# FLR_-_Schematic.net
KiCad netlist of a schematic drawn in EAGLE
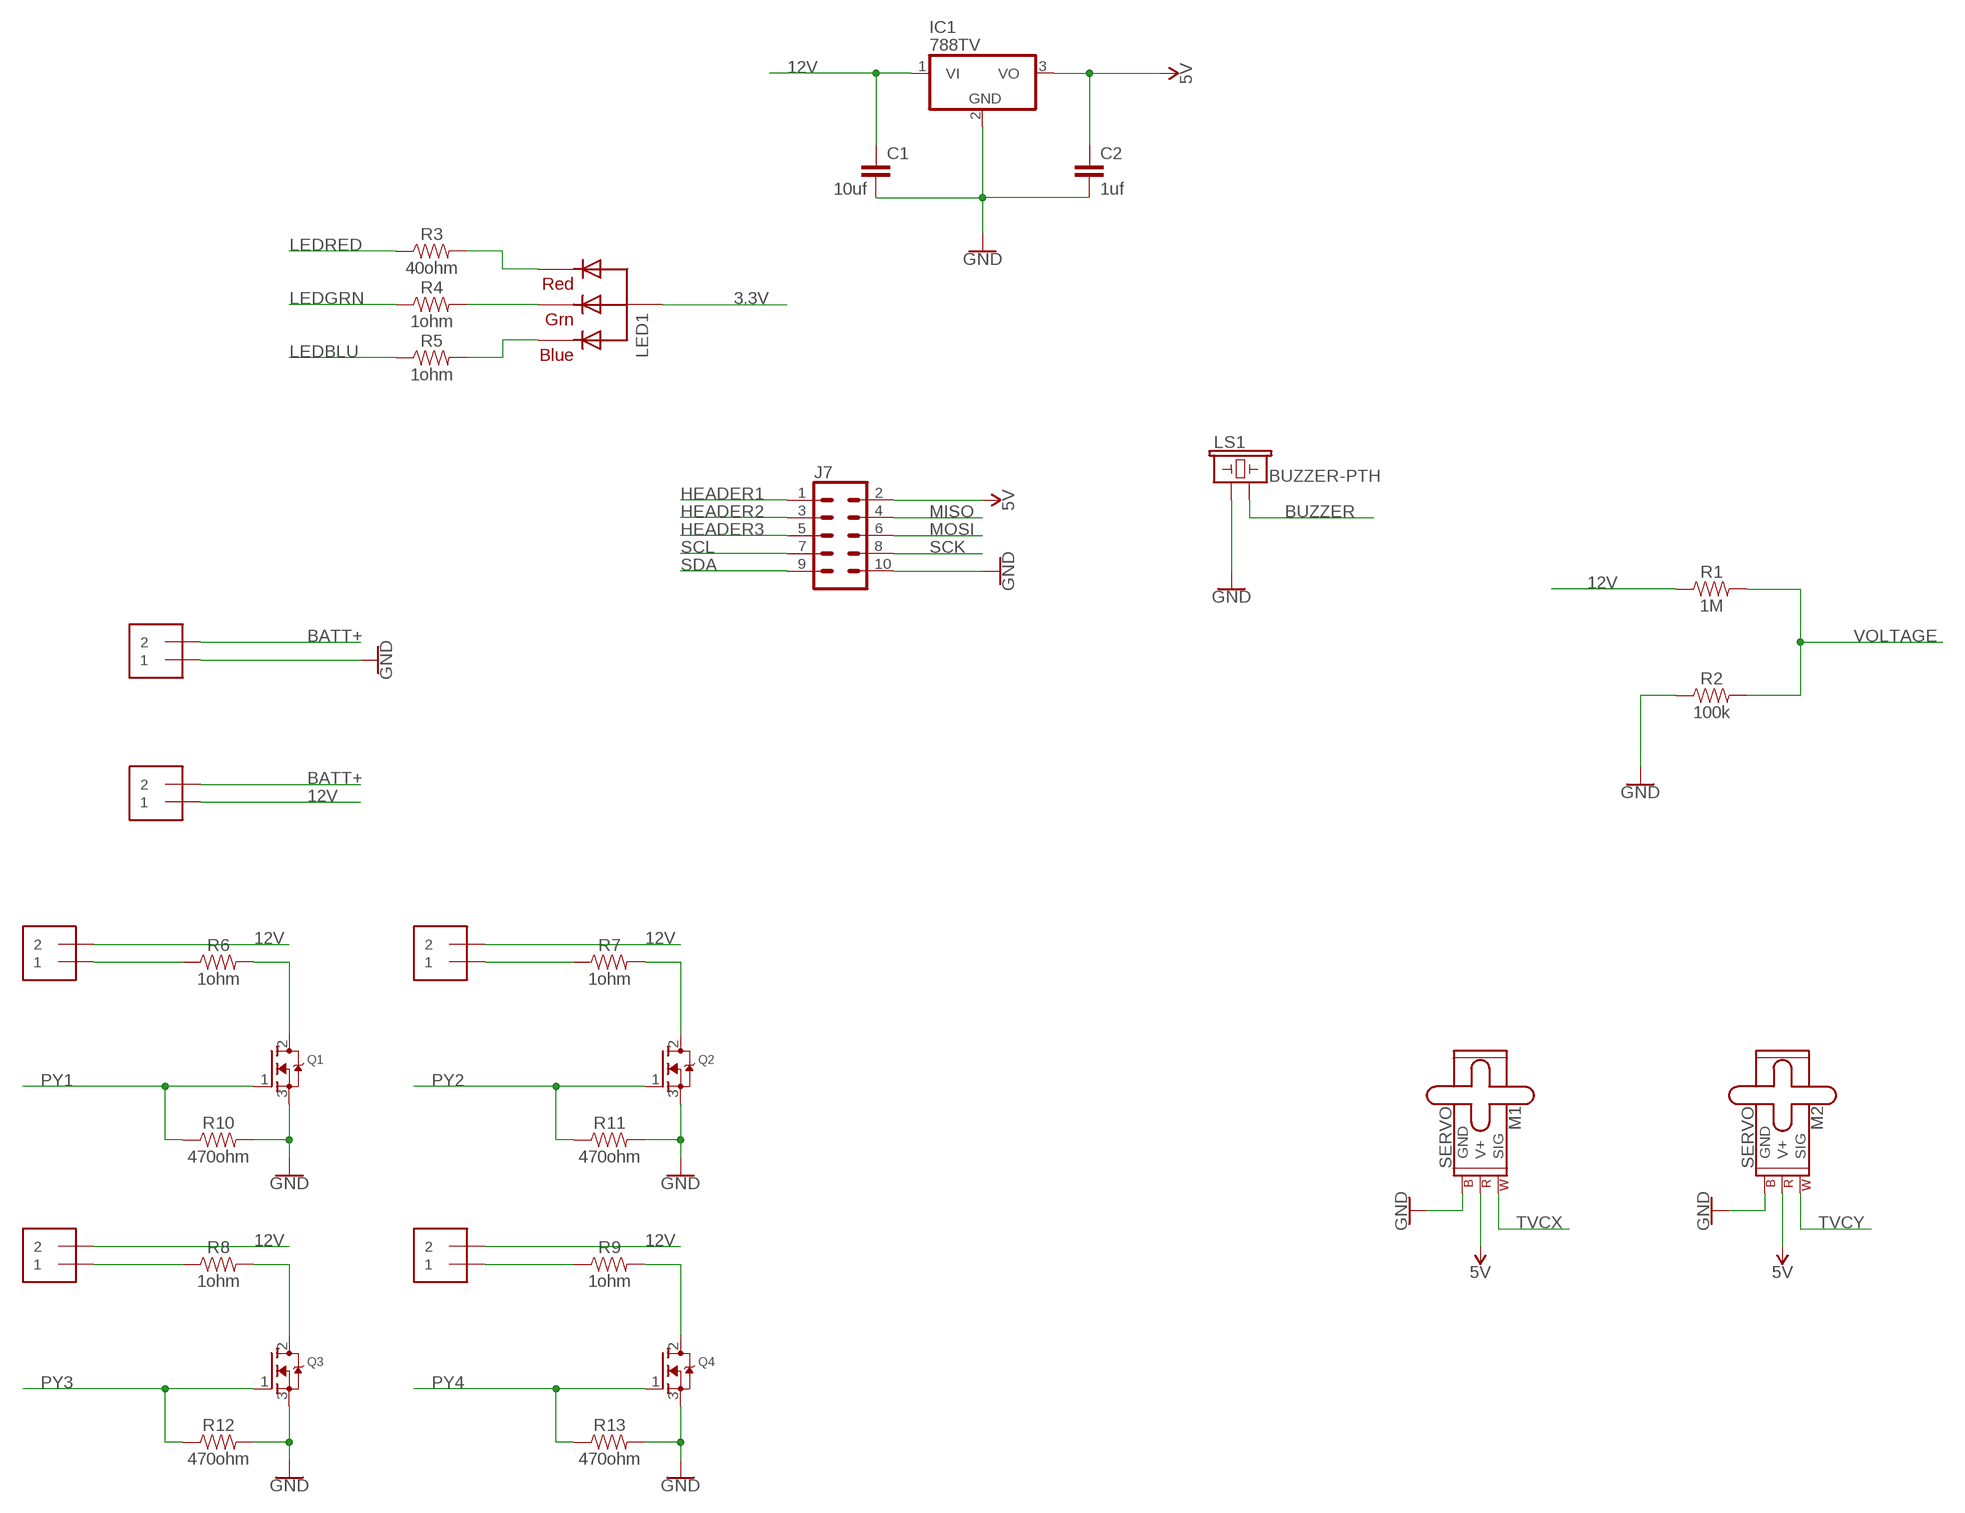
[diagram p0: schematic, sheet 1, part 1 of 2]
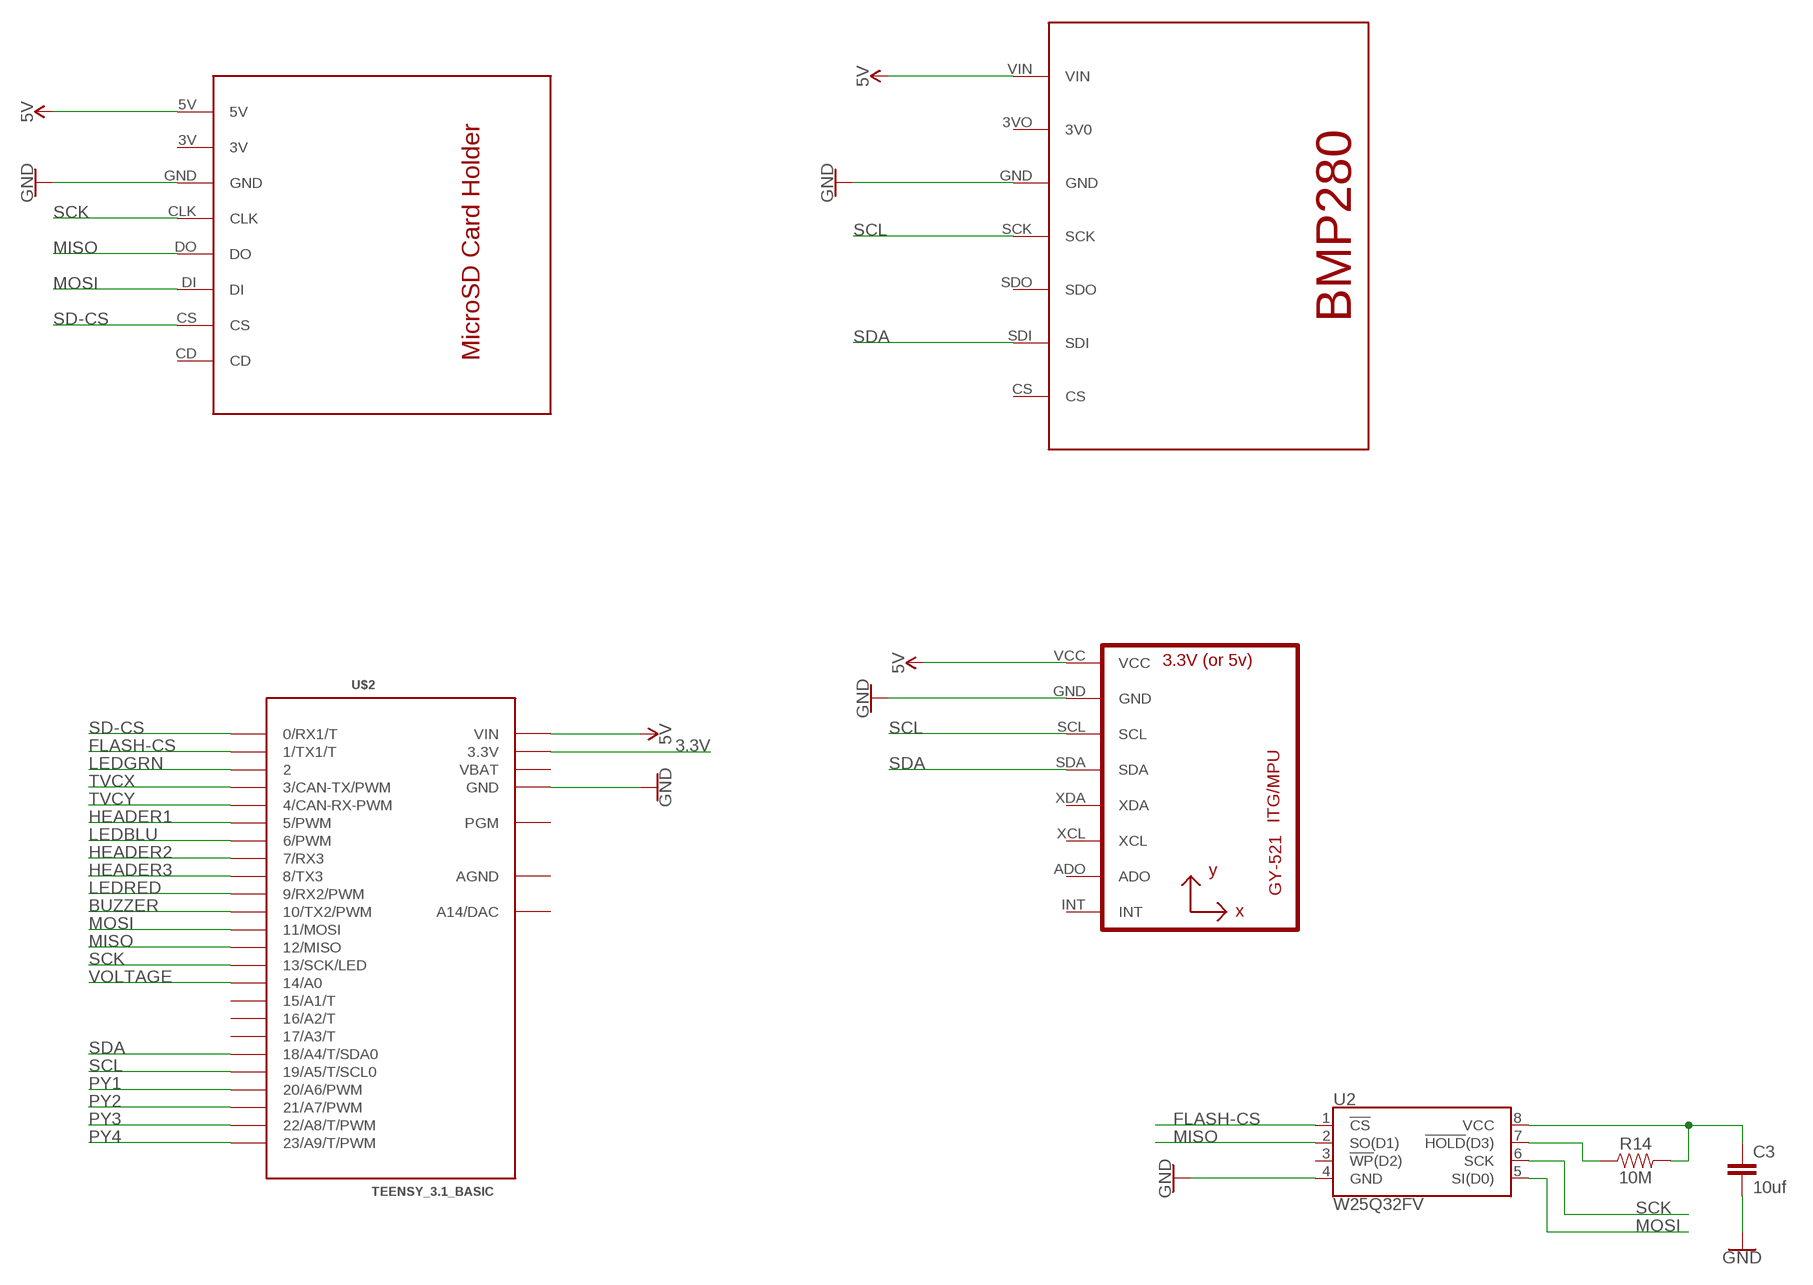
[diagram p1: schematic, sheet 1, part 2 of 2]

(export (version "E")
  (design (tool "Eeschema 10.0.6"))
  (components
    (comp (ref "C1")
      (value "10uf")
      (footprint "eagle-import:CAP-PTH-2.54")
      (libsource (lib "eagle-import") (part "22PF-PTH-2.54MM-200V-5%"))
    )
    (comp (ref "C2")
      (value "1uf")
      (footprint "eagle-import:CAP-PTH-2.54")
      (libsource (lib "eagle-import") (part "22PF-PTH-2.54MM-200V-5%"))
    )
    (comp (ref "C3")
      (value "10uf")
      (footprint "eagle-import:CAP-PTH-2.54")
      (libsource (lib "eagle-import") (part "22PF-PTH-2.54MM-200V-5%"))
    )
    (comp (ref "IC1")
      (value "788TV")
      (footprint "eagle-import:TO220V")
      (libsource (lib "eagle-import") (part "78TV8"))
    )
    (comp (ref "J1")
      (value "1X2-3.5MM")
      (footprint "eagle-import:1X2-3.5MM")
      (libsource (lib "eagle-import") (part "1X2-3.5MM"))
    )
    (comp (ref "J2")
      (value "1X2-3.5MM")
      (footprint "eagle-import:1X2-3.5MM")
      (libsource (lib "eagle-import") (part "1X2-3.5MM"))
    )
    (comp (ref "J3")
      (value "1X2-3.5MM")
      (footprint "eagle-import:1X2-3.5MM")
      (libsource (lib "eagle-import") (part "1X2-3.5MM"))
    )
    (comp (ref "J4")
      (value "1X2-3.5MM")
      (footprint "eagle-import:1X2-3.5MM")
      (libsource (lib "eagle-import") (part "1X2-3.5MM"))
    )
    (comp (ref "J5")
      (value "1X2-3.5MM")
      (footprint "eagle-import:1X2-3.5MM")
      (libsource (lib "eagle-import") (part "1X2-3.5MM"))
    )
    (comp (ref "J6")
      (value "1X2-3.5MM")
      (footprint "eagle-import:1X2-3.5MM")
      (libsource (lib "eagle-import") (part "1X2-3.5MM"))
    )
    (comp (ref "J7")
      (value "CONN_05X2NO_SILK")
      (footprint "eagle-import:2X5_NOSILK")
      (libsource (lib "eagle-import") (part "CONN_05X2NO_SILK"))
    )
    (comp (ref "LED1")
      (value "RGBLED_CA-5MM")
      (footprint "eagle-import:LED5MMRGB")
      (libsource (lib "eagle-import") (part "RGBLED_CA-5MM"))
    )
    (comp (ref "LS1")
      (value "BUZZER-PTH")
      (footprint "eagle-import:BUZZER-12MM")
      (libsource (lib "eagle-import") (part "BUZZER-PTH"))
    )
    (comp (ref "M1")
      (value "SERVO")
      (footprint "eagle-import:1X03")
      (libsource (lib "eagle-import") (part "SERVO"))
    )
    (comp (ref "M2")
      (value "SERVO")
      (footprint "eagle-import:1X03")
      (libsource (lib "eagle-import") (part "SERVO"))
    )
    (comp (ref "Q1")
      (value "MOSFET-NGDS_TO220V")
      (footprint "eagle-import:TO220V")
      (libsource (lib "eagle-import") (part "MOSFET-NGDS_TO220V"))
    )
    (comp (ref "Q2")
      (value "MOSFET-NGDS_TO220V")
      (footprint "eagle-import:TO220V")
      (libsource (lib "eagle-import") (part "MOSFET-NGDS_TO220V"))
    )
    (comp (ref "Q3")
      (value "MOSFET-NGDS_TO220V")
      (footprint "eagle-import:TO220V")
      (libsource (lib "eagle-import") (part "MOSFET-NGDS_TO220V"))
    )
    (comp (ref "Q4")
      (value "MOSFET-NGDS_TO220V")
      (footprint "eagle-import:TO220V")
      (libsource (lib "eagle-import") (part "MOSFET-NGDS_TO220V"))
    )
    (comp (ref "R1")
      (value "1M")
      (footprint "eagle-import:AXIAL-0.3")
      (libsource (lib "eagle-import") (part "10MOHM-HORIZ-1/4W-5%"))
    )
    (comp (ref "R2")
      (value "100k")
      (footprint "eagle-import:AXIAL-0.3")
      (libsource (lib "eagle-import") (part "10MOHM-HORIZ-1/4W-5%"))
    )
    (comp (ref "R3")
      (value "40ohm")
      (footprint "eagle-import:AXIAL-0.3")
      (libsource (lib "eagle-import") (part "10MOHM-HORIZ-1/4W-5%"))
    )
    (comp (ref "R4")
      (value "1ohm")
      (footprint "eagle-import:AXIAL-0.3")
      (libsource (lib "eagle-import") (part "10MOHM-HORIZ-1/4W-5%"))
    )
    (comp (ref "R5")
      (value "1ohm")
      (footprint "eagle-import:AXIAL-0.3")
      (libsource (lib "eagle-import") (part "10MOHM-HORIZ-1/4W-5%"))
    )
    (comp (ref "R6")
      (value "1ohm")
      (footprint "eagle-import:AXIAL-0.3")
      (libsource (lib "eagle-import") (part "10MOHM-HORIZ-1/4W-5%"))
    )
    (comp (ref "R7")
      (value "1ohm")
      (footprint "eagle-import:AXIAL-0.3")
      (libsource (lib "eagle-import") (part "10MOHM-HORIZ-1/4W-5%"))
    )
    (comp (ref "R8")
      (value "1ohm")
      (footprint "eagle-import:AXIAL-0.3")
      (libsource (lib "eagle-import") (part "10MOHM-HORIZ-1/4W-5%"))
    )
    (comp (ref "R9")
      (value "1ohm")
      (footprint "eagle-import:AXIAL-0.3")
      (libsource (lib "eagle-import") (part "10MOHM-HORIZ-1/4W-5%"))
    )
    (comp (ref "R10")
      (value "470ohm")
      (footprint "eagle-import:AXIAL-0.3")
      (libsource (lib "eagle-import") (part "10MOHM-HORIZ-1/4W-5%"))
    )
    (comp (ref "R11")
      (value "470ohm")
      (footprint "eagle-import:AXIAL-0.3")
      (libsource (lib "eagle-import") (part "10MOHM-HORIZ-1/4W-5%"))
    )
    (comp (ref "R12")
      (value "470ohm")
      (footprint "eagle-import:AXIAL-0.3")
      (libsource (lib "eagle-import") (part "10MOHM-HORIZ-1/4W-5%"))
    )
    (comp (ref "R13")
      (value "470ohm")
      (footprint "eagle-import:AXIAL-0.3")
      (libsource (lib "eagle-import") (part "10MOHM-HORIZ-1/4W-5%"))
    )
    (comp (ref "R14")
      (value "10M")
      (footprint "eagle-import:AXIAL-0.3")
      (libsource (lib "eagle-import") (part "10MOHM-HORIZ-1/4W-5%"))
    )
    (comp (ref "U$1")
      (value "MICROSDCARD")
      (footprint "eagle-import:MICROSDCARD")
      (libsource (lib "eagle-import") (part "MICROSDCARD"))
    )
    (comp (ref "U$2")
      (value "TEENSY_3.1_BASIC")
      (footprint "eagle-import:TEENSY_3.1_BASIC")
      (libsource (lib "eagle-import") (part "TEENSY_3.1_BASIC"))
    )
    (comp (ref "U$3")
      (value "BMP280")
      (footprint "eagle-import:BMP280")
      (libsource (lib "eagle-import") (part "BMP280"))
    )
    (comp (ref "U1")
      (value "GY-521MPU6050")
      (footprint "eagle-import:GY-521")
      (libsource (lib "eagle-import") (part "GY-521MPU6050"))
    )
    (comp (ref "U2")
      (value "W25Q32FV")
      (footprint "eagle-import:SOIC-8")
      (libsource (lib "eagle-import") (part "W25Q32FVSS"))
    )
  )
  (nets
    (net (code "1") (name "/3.3V") (class "Default")
      (node (ref "LED1") (pin "2") (pinfunction "VCC_2") (pintype "bidirectional"))
      (node (ref "U$2") (pin "3.3V") (pinfunction "3.3V_3.3V") (pintype "power_in"))
      (node (ref "U$2") (pin "3.3V1") (pinfunction "3.3V_3.3V1") (pintype "power_in"))
    )
    (net (code "2") (name "/12V") (class "Default")
      (node (ref "C1") (pin "1") (pinfunction "1_1") (pintype "passive"))
      (node (ref "IC1") (pin "1") (pinfunction "VI_1") (pintype "input"))
      (node (ref "J2") (pin "1") (pinfunction "1_1") (pintype "passive"))
      (node (ref "J3") (pin "2") (pinfunction "2_2") (pintype "passive"))
      (node (ref "J4") (pin "2") (pinfunction "2_2") (pintype "passive"))
      (node (ref "J5") (pin "2") (pinfunction "2_2") (pintype "passive"))
      (node (ref "J6") (pin "2") (pinfunction "2_2") (pintype "passive"))
      (node (ref "R1") (pin "P$1") (pinfunction "1_P$1") (pintype "passive"))
    )
    (net (code "3") (name "/AGND") (class "Default")
      (node (ref "U$2") (pin "AGND") (pinfunction "AGND_AGND") (pintype "power_in"))
    )
    (net (code "4") (name "/BATT+") (class "Default")
      (node (ref "J1") (pin "2") (pinfunction "2_2") (pintype "passive"))
      (node (ref "J2") (pin "2") (pinfunction "2_2") (pintype "passive"))
    )
    (net (code "5") (name "/BUZZER") (class "Default")
      (node (ref "LS1") (pin "-") (pinfunction "2_-") (pintype "passive"))
      (node (ref "U$2") (pin "10") (pinfunction "10/TX2/PWM_10") (pintype "bidirectional"))
    )
    (net (code "6") (name "/FLASH-CS") (class "Default")
      (node (ref "U$2") (pin "1") (pinfunction "1/TX1/T_1") (pintype "bidirectional"))
      (node (ref "U2") (pin "1") (pinfunction "~{CS}_1") (pintype "bidirectional"))
    )
    (net (code "7") (name "/HEADER1") (class "Default")
      (node (ref "J7") (pin "1") (pinfunction "1_1") (pintype "passive"))
      (node (ref "U$2") (pin "5") (pinfunction "5/PWM_5") (pintype "bidirectional"))
    )
    (net (code "8") (name "/HEADER2") (class "Default")
      (node (ref "J7") (pin "3") (pinfunction "3_3") (pintype "passive"))
      (node (ref "U$2") (pin "7") (pinfunction "7/RX3_7") (pintype "bidirectional"))
    )
    (net (code "9") (name "/HEADER3") (class "Default")
      (node (ref "J7") (pin "5") (pinfunction "5_5") (pintype "passive"))
      (node (ref "U$2") (pin "8") (pinfunction "8/TX3_8") (pintype "bidirectional"))
    )
    (net (code "10") (name "/LEDBLU") (class "Default")
      (node (ref "R5") (pin "P$1") (pinfunction "1_P$1") (pintype "passive"))
      (node (ref "U$2") (pin "6") (pinfunction "6/PWM_6") (pintype "bidirectional"))
    )
    (net (code "11") (name "/LEDGRN") (class "Default")
      (node (ref "R4") (pin "P$1") (pinfunction "1_P$1") (pintype "passive"))
      (node (ref "U$2") (pin "2") (pinfunction "2_2") (pintype "bidirectional"))
    )
    (net (code "12") (name "/LEDRED") (class "Default")
      (node (ref "R3") (pin "P$1") (pinfunction "1_P$1") (pintype "passive"))
      (node (ref "U$2") (pin "9") (pinfunction "9/RX2/PWM_9") (pintype "bidirectional"))
    )
    (net (code "13") (name "/MISO") (class "Default")
      (node (ref "J7") (pin "4") (pinfunction "4_4") (pintype "passive"))
      (node (ref "U$1") (pin "DO") (pinfunction "DO_DO") (pintype "bidirectional"))
      (node (ref "U$2") (pin "12") (pinfunction "12/MISO_12") (pintype "bidirectional"))
      (node (ref "U2") (pin "2") (pinfunction "SO(D1)_2") (pintype "bidirectional"))
    )
    (net (code "14") (name "/MOSI") (class "Default")
      (node (ref "J7") (pin "6") (pinfunction "6_6") (pintype "passive"))
      (node (ref "U$1") (pin "DI") (pinfunction "DI_DI") (pintype "bidirectional"))
      (node (ref "U$2") (pin "11") (pinfunction "11/MOSI_11") (pintype "bidirectional"))
      (node (ref "U2") (pin "5") (pinfunction "SI(D0)_5") (pintype "bidirectional"))
    )
    (net (code "15") (name "/PY1") (class "Default")
      (node (ref "Q1") (pin "1") (pinfunction "G_1") (pintype "bidirectional"))
      (node (ref "R10") (pin "P$1") (pinfunction "1_P$1") (pintype "passive"))
      (node (ref "U$2") (pin "20/A6") (pinfunction "20/A6/PWM_20/A6") (pintype "bidirectional"))
    )
    (net (code "16") (name "/PY2") (class "Default")
      (node (ref "Q2") (pin "1") (pinfunction "G_1") (pintype "bidirectional"))
      (node (ref "R11") (pin "P$1") (pinfunction "1_P$1") (pintype "passive"))
      (node (ref "U$2") (pin "21/A7") (pinfunction "21/A7/PWM_21/A7") (pintype "bidirectional"))
    )
    (net (code "17") (name "/PY3") (class "Default")
      (node (ref "Q3") (pin "1") (pinfunction "G_1") (pintype "bidirectional"))
      (node (ref "R12") (pin "P$1") (pinfunction "1_P$1") (pintype "passive"))
      (node (ref "U$2") (pin "22/A8") (pinfunction "22/A8/T/PWM_22/A8") (pintype "bidirectional"))
    )
    (net (code "18") (name "/PY4") (class "Default")
      (node (ref "Q4") (pin "1") (pinfunction "G_1") (pintype "bidirectional"))
      (node (ref "R13") (pin "P$1") (pinfunction "1_P$1") (pintype "passive"))
      (node (ref "U$2") (pin "23/A9") (pinfunction "23/A9/T/PWM_23/A9") (pintype "bidirectional"))
    )
    (net (code "19") (name "/SCK") (class "Default")
      (node (ref "J7") (pin "8") (pinfunction "8_8") (pintype "passive"))
      (node (ref "U$1") (pin "CLK") (pinfunction "CLK_CLK") (pintype "bidirectional"))
      (node (ref "U$2") (pin "13") (pinfunction "13/SCK/LED_13") (pintype "bidirectional"))
      (node (ref "U2") (pin "6") (pinfunction "SCK_6") (pintype "bidirectional"))
    )
    (net (code "20") (name "/SCL") (class "Default")
      (node (ref "J7") (pin "7") (pinfunction "7_7") (pintype "passive"))
      (node (ref "U$2") (pin "19/A5") (pinfunction "19/A5/T/SCL0_19/A5") (pintype "bidirectional"))
      (node (ref "U$3") (pin "SCK") (pinfunction "SCK_SCK") (pintype "bidirectional"))
      (node (ref "U1") (pin "SCL") (pinfunction "SCL_SCL") (pintype "bidirectional"))
    )
    (net (code "21") (name "/SD-CS") (class "Default")
      (node (ref "U$1") (pin "CS") (pinfunction "CS_CS") (pintype "bidirectional"))
      (node (ref "U$2") (pin "0") (pinfunction "0/RX1/T_0") (pintype "bidirectional"))
    )
    (net (code "22") (name "/SDA") (class "Default")
      (node (ref "J7") (pin "9") (pinfunction "9_9") (pintype "passive"))
      (node (ref "U$2") (pin "18/A4") (pinfunction "18/A4/T/SDA0_18/A4") (pintype "bidirectional"))
      (node (ref "U$3") (pin "SDI") (pinfunction "SDI_SDI") (pintype "bidirectional"))
      (node (ref "U1") (pin "SDA") (pinfunction "SDA_SDA") (pintype "bidirectional"))
    )
    (net (code "23") (name "/TVCX") (class "Default")
      (node (ref "M1") (pin "1") (pinfunction "SIG_1") (pintype "bidirectional"))
      (node (ref "U$2") (pin "3") (pinfunction "3/CAN-TX/PWM_3") (pintype "bidirectional"))
    )
    (net (code "24") (name "/TVCY") (class "Default")
      (node (ref "M2") (pin "1") (pinfunction "SIG_1") (pintype "bidirectional"))
      (node (ref "U$2") (pin "4") (pinfunction "4/CAN-RX-PWM_4") (pintype "bidirectional"))
    )
    (net (code "25") (name "/VBAT") (class "Default")
      (node (ref "U$2") (pin "VBAT") (pinfunction "VBAT_VBAT") (pintype "power_in"))
    )
    (net (code "26") (name "/VOLTAGE") (class "Default")
      (node (ref "R1") (pin "P$2") (pinfunction "2_P$2") (pintype "passive"))
      (node (ref "R2") (pin "P$2") (pinfunction "2_P$2") (pintype "passive"))
      (node (ref "U$2") (pin "14/A0") (pinfunction "14/A0_14/A0") (pintype "bidirectional"))
    )
    (net (code "27") (name "5V") (class "Default")
      (node (ref "C2") (pin "1") (pinfunction "1_1") (pintype "passive"))
      (node (ref "IC1") (pin "3") (pinfunction "VO_3") (pintype "passive"))
      (node (ref "J7") (pin "2") (pinfunction "2_2") (pintype "passive"))
      (node (ref "M1") (pin "2") (pinfunction "V+_2") (pintype "bidirectional"))
      (node (ref "M2") (pin "2") (pinfunction "V+_2") (pintype "bidirectional"))
      (node (ref "U$1") (pin "5V") (pinfunction "5V_5V") (pintype "bidirectional"))
      (node (ref "U$2") (pin "VIN") (pinfunction "VIN_VIN") (pintype "power_in"))
      (node (ref "U$3") (pin "VIN") (pinfunction "VIN_VIN") (pintype "bidirectional"))
      (node (ref "U1") (pin "VCC") (pinfunction "VCC_VCC") (pintype "bidirectional"))
    )
    (net (code "28") (name "GND") (class "Default")
      (node (ref "C1") (pin "2") (pinfunction "2_2") (pintype "passive"))
      (node (ref "C2") (pin "2") (pinfunction "2_2") (pintype "passive"))
      (node (ref "C3") (pin "2") (pinfunction "2_2") (pintype "passive"))
      (node (ref "IC1") (pin "2") (pinfunction "GND_2") (pintype "passive"))
      (node (ref "J1") (pin "1") (pinfunction "1_1") (pintype "passive"))
      (node (ref "J7") (pin "10") (pinfunction "10_10") (pintype "passive"))
      (node (ref "LS1") (pin "+") (pinfunction "1_+") (pintype "passive"))
      (node (ref "M1") (pin "3") (pinfunction "GND_3") (pintype "bidirectional"))
      (node (ref "M2") (pin "3") (pinfunction "GND_3") (pintype "bidirectional"))
      (node (ref "Q1") (pin "3") (pinfunction "S_3") (pintype "bidirectional"))
      (node (ref "Q2") (pin "3") (pinfunction "S_3") (pintype "bidirectional"))
      (node (ref "Q3") (pin "3") (pinfunction "S_3") (pintype "bidirectional"))
      (node (ref "Q4") (pin "3") (pinfunction "S_3") (pintype "bidirectional"))
      (node (ref "R10") (pin "P$2") (pinfunction "2_P$2") (pintype "passive"))
      (node (ref "R11") (pin "P$2") (pinfunction "2_P$2") (pintype "passive"))
      (node (ref "R12") (pin "P$2") (pinfunction "2_P$2") (pintype "passive"))
      (node (ref "R13") (pin "P$2") (pinfunction "2_P$2") (pintype "passive"))
      (node (ref "R2") (pin "P$1") (pinfunction "1_P$1") (pintype "passive"))
      (node (ref "U$1") (pin "GND") (pinfunction "GND_GND") (pintype "bidirectional"))
      (node (ref "U$2") (pin "GND") (pinfunction "GND_GND") (pintype "power_in"))
      (node (ref "U$2") (pin "GND1") (pinfunction "GND_GND1") (pintype "power_in"))
      (node (ref "U$3") (pin "GND") (pinfunction "GND_GND") (pintype "bidirectional"))
      (node (ref "U1") (pin "GND") (pinfunction "GND_GND") (pintype "bidirectional"))
      (node (ref "U2") (pin "4") (pinfunction "GND_4") (pintype "bidirectional"))
    )
    (net (code "29") (name "Net-(LED1-BLUE)") (class "Default")
      (node (ref "LED1") (pin "4") (pinfunction "BLUE_4") (pintype "bidirectional"))
      (node (ref "R5") (pin "P$2") (pinfunction "2_P$2") (pintype "passive"))
    )
    (net (code "30") (name "Net-(LED1-GREEN)") (class "Default")
      (node (ref "LED1") (pin "3") (pinfunction "GREEN_3") (pintype "bidirectional"))
      (node (ref "R4") (pin "P$2") (pinfunction "2_P$2") (pintype "passive"))
    )
    (net (code "31") (name "Net-(LED1-RED)") (class "Default")
      (node (ref "LED1") (pin "1") (pinfunction "RED_1") (pintype "bidirectional"))
      (node (ref "R3") (pin "P$2") (pinfunction "2_P$2") (pintype "passive"))
    )
    (net (code "32") (name "Net-(Q1-D)") (class "Default")
      (node (ref "Q1") (pin "2") (pinfunction "D_2") (pintype "bidirectional"))
      (node (ref "R6") (pin "P$2") (pinfunction "2_P$2") (pintype "passive"))
    )
    (net (code "33") (name "Net-(Q2-D)") (class "Default")
      (node (ref "Q2") (pin "2") (pinfunction "D_2") (pintype "bidirectional"))
      (node (ref "R7") (pin "P$2") (pinfunction "2_P$2") (pintype "passive"))
    )
    (net (code "34") (name "Net-(Q3-D)") (class "Default")
      (node (ref "Q3") (pin "2") (pinfunction "D_2") (pintype "bidirectional"))
      (node (ref "R8") (pin "P$2") (pinfunction "2_P$2") (pintype "passive"))
    )
    (net (code "35") (name "Net-(Q4-D)") (class "Default")
      (node (ref "Q4") (pin "2") (pinfunction "D_2") (pintype "bidirectional"))
      (node (ref "R9") (pin "P$2") (pinfunction "2_P$2") (pintype "passive"))
    )
    (net (code "36") (name "Net-(R6-1)") (class "Default")
      (node (ref "J3") (pin "1") (pinfunction "1_1") (pintype "passive"))
      (node (ref "R6") (pin "P$1") (pinfunction "1_P$1") (pintype "passive"))
    )
    (net (code "37") (name "Net-(R7-1)") (class "Default")
      (node (ref "J4") (pin "1") (pinfunction "1_1") (pintype "passive"))
      (node (ref "R7") (pin "P$1") (pinfunction "1_P$1") (pintype "passive"))
    )
    (net (code "38") (name "Net-(R8-1)") (class "Default")
      (node (ref "J5") (pin "1") (pinfunction "1_1") (pintype "passive"))
      (node (ref "R8") (pin "P$1") (pinfunction "1_P$1") (pintype "passive"))
    )
    (net (code "39") (name "Net-(R9-1)") (class "Default")
      (node (ref "J6") (pin "1") (pinfunction "1_1") (pintype "passive"))
      (node (ref "R9") (pin "P$1") (pinfunction "1_P$1") (pintype "passive"))
    )
    (net (code "40") (name "Net-(R14-1)") (class "Default")
      (node (ref "R14") (pin "P$1") (pinfunction "1_P$1") (pintype "passive"))
      (node (ref "U2") (pin "7") (pinfunction "~{HOLD}(D3)_7") (pintype "bidirectional"))
    )
    (net (code "41") (name "Net-(R14-2)") (class "Default")
      (node (ref "C3") (pin "1") (pinfunction "1_1") (pintype "passive"))
      (node (ref "R14") (pin "P$2") (pinfunction "2_P$2") (pintype "passive"))
      (node (ref "U2") (pin "8") (pinfunction "VCC_8") (pintype "bidirectional"))
    )
    (net (code "42") (name "unconnected-(U$1-Pad3V)") (class "Default")
      (node (ref "U$1") (pin "3V") (pinfunction "3V_3V") (pintype "bidirectional"))
    )
    (net (code "43") (name "unconnected-(U$1-PadCD)") (class "Default")
      (node (ref "U$1") (pin "CD") (pinfunction "CD_CD") (pintype "bidirectional"))
    )
    (net (code "44") (name "unconnected-(U$2-15{slash}A1{slash}T-Pad15{slash}A1)") (class "Default")
      (node (ref "U$2") (pin "15/A1") (pinfunction "15/A1/T_15/A1") (pintype "bidirectional"))
    )
    (net (code "45") (name "unconnected-(U$2-16{slash}A2{slash}T-Pad16{slash}A2)") (class "Default")
      (node (ref "U$2") (pin "16/A2") (pinfunction "16/A2/T_16/A2") (pintype "bidirectional"))
    )
    (net (code "46") (name "unconnected-(U$2-17{slash}A3{slash}T-Pad17{slash}A3)") (class "Default")
      (node (ref "U$2") (pin "17/A3") (pinfunction "17/A3/T_17/A3") (pintype "bidirectional"))
    )
    (net (code "47") (name "unconnected-(U$2-A14{slash}DAC-PadA14)") (class "Default")
      (node (ref "U$2") (pin "A14") (pinfunction "A14/DAC_A14") (pintype "bidirectional"))
    )
    (net (code "48") (name "unconnected-(U$2-PadPGM)") (class "Default")
      (node (ref "U$2") (pin "PGM") (pinfunction "PGM_PGM") (pintype "bidirectional"))
    )
    (net (code "49") (name "unconnected-(U$3-3V0-Pad3VO)") (class "Default")
      (node (ref "U$3") (pin "3VO") (pinfunction "3V0_3VO") (pintype "bidirectional"))
    )
    (net (code "50") (name "unconnected-(U$3-PadCS)") (class "Default")
      (node (ref "U$3") (pin "CS") (pinfunction "CS_CS") (pintype "bidirectional"))
    )
    (net (code "51") (name "unconnected-(U$3-PadSDO)") (class "Default")
      (node (ref "U$3") (pin "SDO") (pinfunction "SDO_SDO") (pintype "bidirectional"))
    )
    (net (code "52") (name "unconnected-(U1-PadADO)") (class "Default")
      (node (ref "U1") (pin "ADO") (pinfunction "ADO_ADO") (pintype "bidirectional"))
    )
    (net (code "53") (name "unconnected-(U1-PadINT)") (class "Default")
      (node (ref "U1") (pin "INT") (pinfunction "INT_INT") (pintype "bidirectional"))
    )
    (net (code "54") (name "unconnected-(U1-PadXCL)") (class "Default")
      (node (ref "U1") (pin "XCL") (pinfunction "XCL_XCL") (pintype "bidirectional"))
    )
    (net (code "55") (name "unconnected-(U1-PadXDA)") (class "Default")
      (node (ref "U1") (pin "XDA") (pinfunction "XDA_XDA") (pintype "bidirectional"))
    )
    (net (code "56") (name "unconnected-(U2-~{WP}(D2)-Pad3)") (class "Default")
      (node (ref "U2") (pin "3") (pinfunction "~{WP}(D2)_3") (pintype "bidirectional"))
    )
  )
)
